# daughterboard-schematic.net
KiCad netlist of a schematic drawn in EAGLE
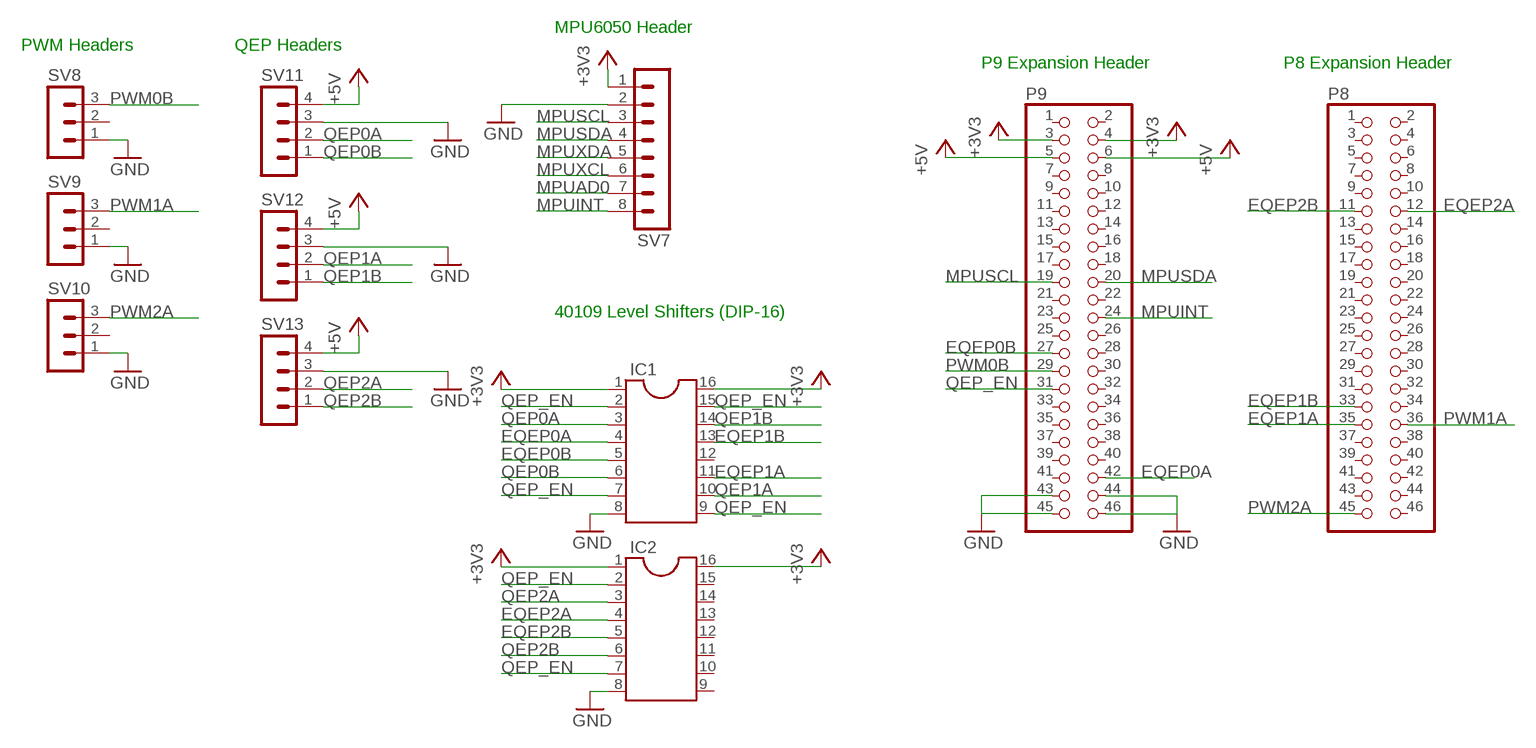
[diagram p0: schematic, sheet 1]

(export (version "E")
  (design (tool "Eeschema 10.0.6"))
  (components
    (comp (ref "IC1")
      (value "DIL16")
      (footprint "eagle-import:DIL16")
      (libsource (lib "eagle-import") (part "DIL16"))
    )
    (comp (ref "IC2")
      (value "DIL16")
      (footprint "eagle-import:DIL16")
      (libsource (lib "eagle-import") (part "DIL16"))
    )
    (comp (ref "P8")
      (value "PINHD-2X23")
      (footprint "eagle-import:2X23")
      (libsource (lib "eagle-import") (part "PINHD-2X23"))
    )
    (comp (ref "P9")
      (value "PINHD-2X23")
      (footprint "eagle-import:2X23")
      (libsource (lib "eagle-import") (part "PINHD-2X23"))
    )
    (comp (ref "SV7")
      (value "MA08-1")
      (footprint "eagle-import:MA08-1")
      (libsource (lib "eagle-import") (part "MA08-1"))
    )
    (comp (ref "SV8")
      (value "MA03-1")
      (footprint "eagle-import:MA03-1")
      (libsource (lib "eagle-import") (part "MA03-1"))
    )
    (comp (ref "SV9")
      (value "MA03-1")
      (footprint "eagle-import:MA03-1")
      (libsource (lib "eagle-import") (part "MA03-1"))
    )
    (comp (ref "SV10")
      (value "MA03-1")
      (footprint "eagle-import:MA03-1")
      (libsource (lib "eagle-import") (part "MA03-1"))
    )
    (comp (ref "SV11")
      (value "MA04-1")
      (footprint "eagle-import:MA04-1")
      (libsource (lib "eagle-import") (part "MA04-1"))
    )
    (comp (ref "SV12")
      (value "MA04-1")
      (footprint "eagle-import:MA04-1")
      (libsource (lib "eagle-import") (part "MA04-1"))
    )
    (comp (ref "SV13")
      (value "MA04-1")
      (footprint "eagle-import:MA04-1")
      (libsource (lib "eagle-import") (part "MA04-1"))
    )
  )
  (nets
    (net (code "1") (name "+3V3") (class "Default")
      (node (ref "IC1") (pin "1") (pinfunction "1_1") (pintype "passive"))
      (node (ref "IC1") (pin "16") (pinfunction "16_16") (pintype "passive"))
      (node (ref "IC2") (pin "1") (pinfunction "1_1") (pintype "passive"))
      (node (ref "IC2") (pin "16") (pinfunction "16_16") (pintype "passive"))
      (node (ref "P9") (pin "3") (pinfunction "3_3") (pintype "passive"))
      (node (ref "P9") (pin "4") (pinfunction "4_4") (pintype "passive"))
      (node (ref "SV7") (pin "1") (pinfunction "1_1") (pintype "passive"))
    )
    (net (code "2") (name "+5V") (class "Default")
      (node (ref "P9") (pin "5") (pinfunction "5_5") (pintype "passive"))
      (node (ref "P9") (pin "6") (pinfunction "6_6") (pintype "passive"))
      (node (ref "SV11") (pin "4") (pinfunction "4_4") (pintype "passive"))
      (node (ref "SV12") (pin "4") (pinfunction "4_4") (pintype "passive"))
      (node (ref "SV13") (pin "4") (pinfunction "4_4") (pintype "passive"))
    )
    (net (code "3") (name "/EQEP0A") (class "Default")
      (node (ref "IC1") (pin "4") (pinfunction "4_4") (pintype "passive"))
      (node (ref "P9") (pin "42") (pinfunction "42_42") (pintype "passive"))
    )
    (net (code "4") (name "/EQEP0B") (class "Default")
      (node (ref "IC1") (pin "5") (pinfunction "5_5") (pintype "passive"))
      (node (ref "P9") (pin "27") (pinfunction "27_27") (pintype "passive"))
    )
    (net (code "5") (name "/EQEP1A") (class "Default")
      (node (ref "IC1") (pin "11") (pinfunction "11_11") (pintype "passive"))
      (node (ref "P8") (pin "35") (pinfunction "35_35") (pintype "passive"))
    )
    (net (code "6") (name "/EQEP1B") (class "Default")
      (node (ref "IC1") (pin "13") (pinfunction "13_13") (pintype "passive"))
      (node (ref "P8") (pin "33") (pinfunction "33_33") (pintype "passive"))
    )
    (net (code "7") (name "/EQEP2A") (class "Default")
      (node (ref "IC2") (pin "4") (pinfunction "4_4") (pintype "passive"))
      (node (ref "P8") (pin "12") (pinfunction "12_12") (pintype "passive"))
    )
    (net (code "8") (name "/EQEP2B") (class "Default")
      (node (ref "IC2") (pin "5") (pinfunction "5_5") (pintype "passive"))
      (node (ref "P8") (pin "11") (pinfunction "11_11") (pintype "passive"))
    )
    (net (code "9") (name "/MPUAD0") (class "Default")
      (node (ref "SV7") (pin "7") (pinfunction "7_7") (pintype "passive"))
    )
    (net (code "10") (name "/MPUINT") (class "Default")
      (node (ref "P9") (pin "24") (pinfunction "24_24") (pintype "passive"))
      (node (ref "SV7") (pin "8") (pinfunction "8_8") (pintype "passive"))
    )
    (net (code "11") (name "/MPUSCL") (class "Default")
      (node (ref "P9") (pin "19") (pinfunction "19_19") (pintype "passive"))
      (node (ref "SV7") (pin "3") (pinfunction "3_3") (pintype "passive"))
    )
    (net (code "12") (name "/MPUSDA") (class "Default")
      (node (ref "P9") (pin "20") (pinfunction "20_20") (pintype "passive"))
      (node (ref "SV7") (pin "4") (pinfunction "4_4") (pintype "passive"))
    )
    (net (code "13") (name "/MPUXCL") (class "Default")
      (node (ref "SV7") (pin "6") (pinfunction "6_6") (pintype "passive"))
    )
    (net (code "14") (name "/MPUXDA") (class "Default")
      (node (ref "SV7") (pin "5") (pinfunction "5_5") (pintype "passive"))
    )
    (net (code "15") (name "/PWM0B") (class "Default")
      (node (ref "P9") (pin "29") (pinfunction "29_29") (pintype "passive"))
      (node (ref "SV8") (pin "3") (pinfunction "3_3") (pintype "passive"))
    )
    (net (code "16") (name "/PWM1A") (class "Default")
      (node (ref "P8") (pin "36") (pinfunction "36_36") (pintype "passive"))
      (node (ref "SV9") (pin "3") (pinfunction "3_3") (pintype "passive"))
    )
    (net (code "17") (name "/PWM2A") (class "Default")
      (node (ref "P8") (pin "45") (pinfunction "45_45") (pintype "passive"))
      (node (ref "SV10") (pin "3") (pinfunction "3_3") (pintype "passive"))
    )
    (net (code "18") (name "/QEP0A") (class "Default")
      (node (ref "IC1") (pin "3") (pinfunction "3_3") (pintype "passive"))
      (node (ref "SV11") (pin "2") (pinfunction "2_2") (pintype "passive"))
    )
    (net (code "19") (name "/QEP0B") (class "Default")
      (node (ref "IC1") (pin "6") (pinfunction "6_6") (pintype "passive"))
      (node (ref "SV11") (pin "1") (pinfunction "1_1") (pintype "passive"))
    )
    (net (code "20") (name "/QEP1A") (class "Default")
      (node (ref "IC1") (pin "10") (pinfunction "10_10") (pintype "passive"))
      (node (ref "SV12") (pin "2") (pinfunction "2_2") (pintype "passive"))
    )
    (net (code "21") (name "/QEP1B") (class "Default")
      (node (ref "IC1") (pin "14") (pinfunction "14_14") (pintype "passive"))
      (node (ref "SV12") (pin "1") (pinfunction "1_1") (pintype "passive"))
    )
    (net (code "22") (name "/QEP2A") (class "Default")
      (node (ref "IC2") (pin "3") (pinfunction "3_3") (pintype "passive"))
      (node (ref "SV13") (pin "2") (pinfunction "2_2") (pintype "passive"))
    )
    (net (code "23") (name "/QEP2B") (class "Default")
      (node (ref "IC2") (pin "6") (pinfunction "6_6") (pintype "passive"))
      (node (ref "SV13") (pin "1") (pinfunction "1_1") (pintype "passive"))
    )
    (net (code "24") (name "/QEP_EN") (class "Default")
      (node (ref "IC1") (pin "15") (pinfunction "15_15") (pintype "passive"))
      (node (ref "IC1") (pin "2") (pinfunction "2_2") (pintype "passive"))
      (node (ref "IC1") (pin "7") (pinfunction "7_7") (pintype "passive"))
      (node (ref "IC1") (pin "9") (pinfunction "9_9") (pintype "passive"))
      (node (ref "IC2") (pin "2") (pinfunction "2_2") (pintype "passive"))
      (node (ref "IC2") (pin "7") (pinfunction "7_7") (pintype "passive"))
      (node (ref "P9") (pin "31") (pinfunction "31_31") (pintype "passive"))
    )
    (net (code "25") (name "GND") (class "Default")
      (node (ref "IC1") (pin "8") (pinfunction "8_8") (pintype "passive"))
      (node (ref "IC2") (pin "8") (pinfunction "8_8") (pintype "passive"))
      (node (ref "P9") (pin "43") (pinfunction "43_43") (pintype "passive"))
      (node (ref "P9") (pin "44") (pinfunction "44_44") (pintype "passive"))
      (node (ref "P9") (pin "45") (pinfunction "45_45") (pintype "passive"))
      (node (ref "P9") (pin "46") (pinfunction "46_46") (pintype "passive"))
      (node (ref "SV10") (pin "1") (pinfunction "1_1") (pintype "passive"))
      (node (ref "SV11") (pin "3") (pinfunction "3_3") (pintype "passive"))
      (node (ref "SV12") (pin "3") (pinfunction "3_3") (pintype "passive"))
      (node (ref "SV13") (pin "3") (pinfunction "3_3") (pintype "passive"))
      (node (ref "SV7") (pin "2") (pinfunction "2_2") (pintype "passive"))
      (node (ref "SV8") (pin "1") (pinfunction "1_1") (pintype "passive"))
      (node (ref "SV9") (pin "1") (pinfunction "1_1") (pintype "passive"))
    )
    (net (code "26") (name "unconnected-(IC1-Pad12)") (class "Default")
      (node (ref "IC1") (pin "12") (pinfunction "12_12") (pintype "passive"))
    )
    (net (code "27") (name "unconnected-(IC2-Pad9)") (class "Default")
      (node (ref "IC2") (pin "9") (pinfunction "9_9") (pintype "passive"))
    )
    (net (code "28") (name "unconnected-(IC2-Pad10)") (class "Default")
      (node (ref "IC2") (pin "10") (pinfunction "10_10") (pintype "passive"))
    )
    (net (code "29") (name "unconnected-(IC2-Pad11)") (class "Default")
      (node (ref "IC2") (pin "11") (pinfunction "11_11") (pintype "passive"))
    )
    (net (code "30") (name "unconnected-(IC2-Pad12)") (class "Default")
      (node (ref "IC2") (pin "12") (pinfunction "12_12") (pintype "passive"))
    )
    (net (code "31") (name "unconnected-(IC2-Pad13)") (class "Default")
      (node (ref "IC2") (pin "13") (pinfunction "13_13") (pintype "passive"))
    )
    (net (code "32") (name "unconnected-(IC2-Pad14)") (class "Default")
      (node (ref "IC2") (pin "14") (pinfunction "14_14") (pintype "passive"))
    )
    (net (code "33") (name "unconnected-(IC2-Pad15)") (class "Default")
      (node (ref "IC2") (pin "15") (pinfunction "15_15") (pintype "passive"))
    )
    (net (code "34") (name "unconnected-(P8-Pad1)") (class "Default")
      (node (ref "P8") (pin "1") (pinfunction "1_1") (pintype "passive"))
    )
    (net (code "35") (name "unconnected-(P8-Pad2)") (class "Default")
      (node (ref "P8") (pin "2") (pinfunction "2_2") (pintype "passive"))
    )
    (net (code "36") (name "unconnected-(P8-Pad3)") (class "Default")
      (node (ref "P8") (pin "3") (pinfunction "3_3") (pintype "passive"))
    )
    (net (code "37") (name "unconnected-(P8-Pad4)") (class "Default")
      (node (ref "P8") (pin "4") (pinfunction "4_4") (pintype "passive"))
    )
    (net (code "38") (name "unconnected-(P8-Pad5)") (class "Default")
      (node (ref "P8") (pin "5") (pinfunction "5_5") (pintype "passive"))
    )
    (net (code "39") (name "unconnected-(P8-Pad6)") (class "Default")
      (node (ref "P8") (pin "6") (pinfunction "6_6") (pintype "passive"))
    )
    (net (code "40") (name "unconnected-(P8-Pad7)") (class "Default")
      (node (ref "P8") (pin "7") (pinfunction "7_7") (pintype "passive"))
    )
    (net (code "41") (name "unconnected-(P8-Pad8)") (class "Default")
      (node (ref "P8") (pin "8") (pinfunction "8_8") (pintype "passive"))
    )
    (net (code "42") (name "unconnected-(P8-Pad9)") (class "Default")
      (node (ref "P8") (pin "9") (pinfunction "9_9") (pintype "passive"))
    )
    (net (code "43") (name "unconnected-(P8-Pad10)") (class "Default")
      (node (ref "P8") (pin "10") (pinfunction "10_10") (pintype "passive"))
    )
    (net (code "44") (name "unconnected-(P8-Pad13)") (class "Default")
      (node (ref "P8") (pin "13") (pinfunction "13_13") (pintype "passive"))
    )
    (net (code "45") (name "unconnected-(P8-Pad14)") (class "Default")
      (node (ref "P8") (pin "14") (pinfunction "14_14") (pintype "passive"))
    )
    (net (code "46") (name "unconnected-(P8-Pad15)") (class "Default")
      (node (ref "P8") (pin "15") (pinfunction "15_15") (pintype "passive"))
    )
    (net (code "47") (name "unconnected-(P8-Pad16)") (class "Default")
      (node (ref "P8") (pin "16") (pinfunction "16_16") (pintype "passive"))
    )
    (net (code "48") (name "unconnected-(P8-Pad17)") (class "Default")
      (node (ref "P8") (pin "17") (pinfunction "17_17") (pintype "passive"))
    )
    (net (code "49") (name "unconnected-(P8-Pad18)") (class "Default")
      (node (ref "P8") (pin "18") (pinfunction "18_18") (pintype "passive"))
    )
    (net (code "50") (name "unconnected-(P8-Pad19)") (class "Default")
      (node (ref "P8") (pin "19") (pinfunction "19_19") (pintype "passive"))
    )
    (net (code "51") (name "unconnected-(P8-Pad20)") (class "Default")
      (node (ref "P8") (pin "20") (pinfunction "20_20") (pintype "passive"))
    )
    (net (code "52") (name "unconnected-(P8-Pad21)") (class "Default")
      (node (ref "P8") (pin "21") (pinfunction "21_21") (pintype "passive"))
    )
    (net (code "53") (name "unconnected-(P8-Pad22)") (class "Default")
      (node (ref "P8") (pin "22") (pinfunction "22_22") (pintype "passive"))
    )
    (net (code "54") (name "unconnected-(P8-Pad23)") (class "Default")
      (node (ref "P8") (pin "23") (pinfunction "23_23") (pintype "passive"))
    )
    (net (code "55") (name "unconnected-(P8-Pad24)") (class "Default")
      (node (ref "P8") (pin "24") (pinfunction "24_24") (pintype "passive"))
    )
    (net (code "56") (name "unconnected-(P8-Pad25)") (class "Default")
      (node (ref "P8") (pin "25") (pinfunction "25_25") (pintype "passive"))
    )
    (net (code "57") (name "unconnected-(P8-Pad26)") (class "Default")
      (node (ref "P8") (pin "26") (pinfunction "26_26") (pintype "passive"))
    )
    (net (code "58") (name "unconnected-(P8-Pad27)") (class "Default")
      (node (ref "P8") (pin "27") (pinfunction "27_27") (pintype "passive"))
    )
    (net (code "59") (name "unconnected-(P8-Pad28)") (class "Default")
      (node (ref "P8") (pin "28") (pinfunction "28_28") (pintype "passive"))
    )
    (net (code "60") (name "unconnected-(P8-Pad29)") (class "Default")
      (node (ref "P8") (pin "29") (pinfunction "29_29") (pintype "passive"))
    )
    (net (code "61") (name "unconnected-(P8-Pad30)") (class "Default")
      (node (ref "P8") (pin "30") (pinfunction "30_30") (pintype "passive"))
    )
    (net (code "62") (name "unconnected-(P8-Pad31)") (class "Default")
      (node (ref "P8") (pin "31") (pinfunction "31_31") (pintype "passive"))
    )
    (net (code "63") (name "unconnected-(P8-Pad32)") (class "Default")
      (node (ref "P8") (pin "32") (pinfunction "32_32") (pintype "passive"))
    )
    (net (code "64") (name "unconnected-(P8-Pad34)") (class "Default")
      (node (ref "P8") (pin "34") (pinfunction "34_34") (pintype "passive"))
    )
    (net (code "65") (name "unconnected-(P8-Pad37)") (class "Default")
      (node (ref "P8") (pin "37") (pinfunction "37_37") (pintype "passive"))
    )
    (net (code "66") (name "unconnected-(P8-Pad38)") (class "Default")
      (node (ref "P8") (pin "38") (pinfunction "38_38") (pintype "passive"))
    )
    (net (code "67") (name "unconnected-(P8-Pad39)") (class "Default")
      (node (ref "P8") (pin "39") (pinfunction "39_39") (pintype "passive"))
    )
    (net (code "68") (name "unconnected-(P8-Pad40)") (class "Default")
      (node (ref "P8") (pin "40") (pinfunction "40_40") (pintype "passive"))
    )
    (net (code "69") (name "unconnected-(P8-Pad41)") (class "Default")
      (node (ref "P8") (pin "41") (pinfunction "41_41") (pintype "passive"))
    )
    (net (code "70") (name "unconnected-(P8-Pad42)") (class "Default")
      (node (ref "P8") (pin "42") (pinfunction "42_42") (pintype "passive"))
    )
    (net (code "71") (name "unconnected-(P8-Pad43)") (class "Default")
      (node (ref "P8") (pin "43") (pinfunction "43_43") (pintype "passive"))
    )
    (net (code "72") (name "unconnected-(P8-Pad44)") (class "Default")
      (node (ref "P8") (pin "44") (pinfunction "44_44") (pintype "passive"))
    )
    (net (code "73") (name "unconnected-(P8-Pad46)") (class "Default")
      (node (ref "P8") (pin "46") (pinfunction "46_46") (pintype "passive"))
    )
    (net (code "74") (name "unconnected-(P9-Pad1)") (class "Default")
      (node (ref "P9") (pin "1") (pinfunction "1_1") (pintype "passive"))
    )
    (net (code "75") (name "unconnected-(P9-Pad2)") (class "Default")
      (node (ref "P9") (pin "2") (pinfunction "2_2") (pintype "passive"))
    )
    (net (code "76") (name "unconnected-(P9-Pad7)") (class "Default")
      (node (ref "P9") (pin "7") (pinfunction "7_7") (pintype "passive"))
    )
    (net (code "77") (name "unconnected-(P9-Pad8)") (class "Default")
      (node (ref "P9") (pin "8") (pinfunction "8_8") (pintype "passive"))
    )
    (net (code "78") (name "unconnected-(P9-Pad9)") (class "Default")
      (node (ref "P9") (pin "9") (pinfunction "9_9") (pintype "passive"))
    )
    (net (code "79") (name "unconnected-(P9-Pad10)") (class "Default")
      (node (ref "P9") (pin "10") (pinfunction "10_10") (pintype "passive"))
    )
    (net (code "80") (name "unconnected-(P9-Pad11)") (class "Default")
      (node (ref "P9") (pin "11") (pinfunction "11_11") (pintype "passive"))
    )
    (net (code "81") (name "unconnected-(P9-Pad12)") (class "Default")
      (node (ref "P9") (pin "12") (pinfunction "12_12") (pintype "passive"))
    )
    (net (code "82") (name "unconnected-(P9-Pad13)") (class "Default")
      (node (ref "P9") (pin "13") (pinfunction "13_13") (pintype "passive"))
    )
    (net (code "83") (name "unconnected-(P9-Pad14)") (class "Default")
      (node (ref "P9") (pin "14") (pinfunction "14_14") (pintype "passive"))
    )
    (net (code "84") (name "unconnected-(P9-Pad15)") (class "Default")
      (node (ref "P9") (pin "15") (pinfunction "15_15") (pintype "passive"))
    )
    (net (code "85") (name "unconnected-(P9-Pad16)") (class "Default")
      (node (ref "P9") (pin "16") (pinfunction "16_16") (pintype "passive"))
    )
    (net (code "86") (name "unconnected-(P9-Pad17)") (class "Default")
      (node (ref "P9") (pin "17") (pinfunction "17_17") (pintype "passive"))
    )
    (net (code "87") (name "unconnected-(P9-Pad18)") (class "Default")
      (node (ref "P9") (pin "18") (pinfunction "18_18") (pintype "passive"))
    )
    (net (code "88") (name "unconnected-(P9-Pad21)") (class "Default")
      (node (ref "P9") (pin "21") (pinfunction "21_21") (pintype "passive"))
    )
    (net (code "89") (name "unconnected-(P9-Pad22)") (class "Default")
      (node (ref "P9") (pin "22") (pinfunction "22_22") (pintype "passive"))
    )
    (net (code "90") (name "unconnected-(P9-Pad23)") (class "Default")
      (node (ref "P9") (pin "23") (pinfunction "23_23") (pintype "passive"))
    )
    (net (code "91") (name "unconnected-(P9-Pad25)") (class "Default")
      (node (ref "P9") (pin "25") (pinfunction "25_25") (pintype "passive"))
    )
    (net (code "92") (name "unconnected-(P9-Pad26)") (class "Default")
      (node (ref "P9") (pin "26") (pinfunction "26_26") (pintype "passive"))
    )
    (net (code "93") (name "unconnected-(P9-Pad28)") (class "Default")
      (node (ref "P9") (pin "28") (pinfunction "28_28") (pintype "passive"))
    )
    (net (code "94") (name "unconnected-(P9-Pad30)") (class "Default")
      (node (ref "P9") (pin "30") (pinfunction "30_30") (pintype "passive"))
    )
    (net (code "95") (name "unconnected-(P9-Pad32)") (class "Default")
      (node (ref "P9") (pin "32") (pinfunction "32_32") (pintype "passive"))
    )
    (net (code "96") (name "unconnected-(P9-Pad33)") (class "Default")
      (node (ref "P9") (pin "33") (pinfunction "33_33") (pintype "passive"))
    )
    (net (code "97") (name "unconnected-(P9-Pad34)") (class "Default")
      (node (ref "P9") (pin "34") (pinfunction "34_34") (pintype "passive"))
    )
    (net (code "98") (name "unconnected-(P9-Pad35)") (class "Default")
      (node (ref "P9") (pin "35") (pinfunction "35_35") (pintype "passive"))
    )
    (net (code "99") (name "unconnected-(P9-Pad36)") (class "Default")
      (node (ref "P9") (pin "36") (pinfunction "36_36") (pintype "passive"))
    )
    (net (code "100") (name "unconnected-(P9-Pad37)") (class "Default")
      (node (ref "P9") (pin "37") (pinfunction "37_37") (pintype "passive"))
    )
    (net (code "101") (name "unconnected-(P9-Pad38)") (class "Default")
      (node (ref "P9") (pin "38") (pinfunction "38_38") (pintype "passive"))
    )
    (net (code "102") (name "unconnected-(P9-Pad39)") (class "Default")
      (node (ref "P9") (pin "39") (pinfunction "39_39") (pintype "passive"))
    )
    (net (code "103") (name "unconnected-(P9-Pad40)") (class "Default")
      (node (ref "P9") (pin "40") (pinfunction "40_40") (pintype "passive"))
    )
    (net (code "104") (name "unconnected-(P9-Pad41)") (class "Default")
      (node (ref "P9") (pin "41") (pinfunction "41_41") (pintype "passive"))
    )
    (net (code "105") (name "unconnected-(SV8-Pad2)") (class "Default")
      (node (ref "SV8") (pin "2") (pinfunction "2_2") (pintype "passive"))
    )
    (net (code "106") (name "unconnected-(SV9-Pad2)") (class "Default")
      (node (ref "SV9") (pin "2") (pinfunction "2_2") (pintype "passive"))
    )
    (net (code "107") (name "unconnected-(SV10-Pad2)") (class "Default")
      (node (ref "SV10") (pin "2") (pinfunction "2_2") (pintype "passive"))
    )
  )
)
